# robotario-2.net
KiCad netlist of a schematic drawn in EAGLE
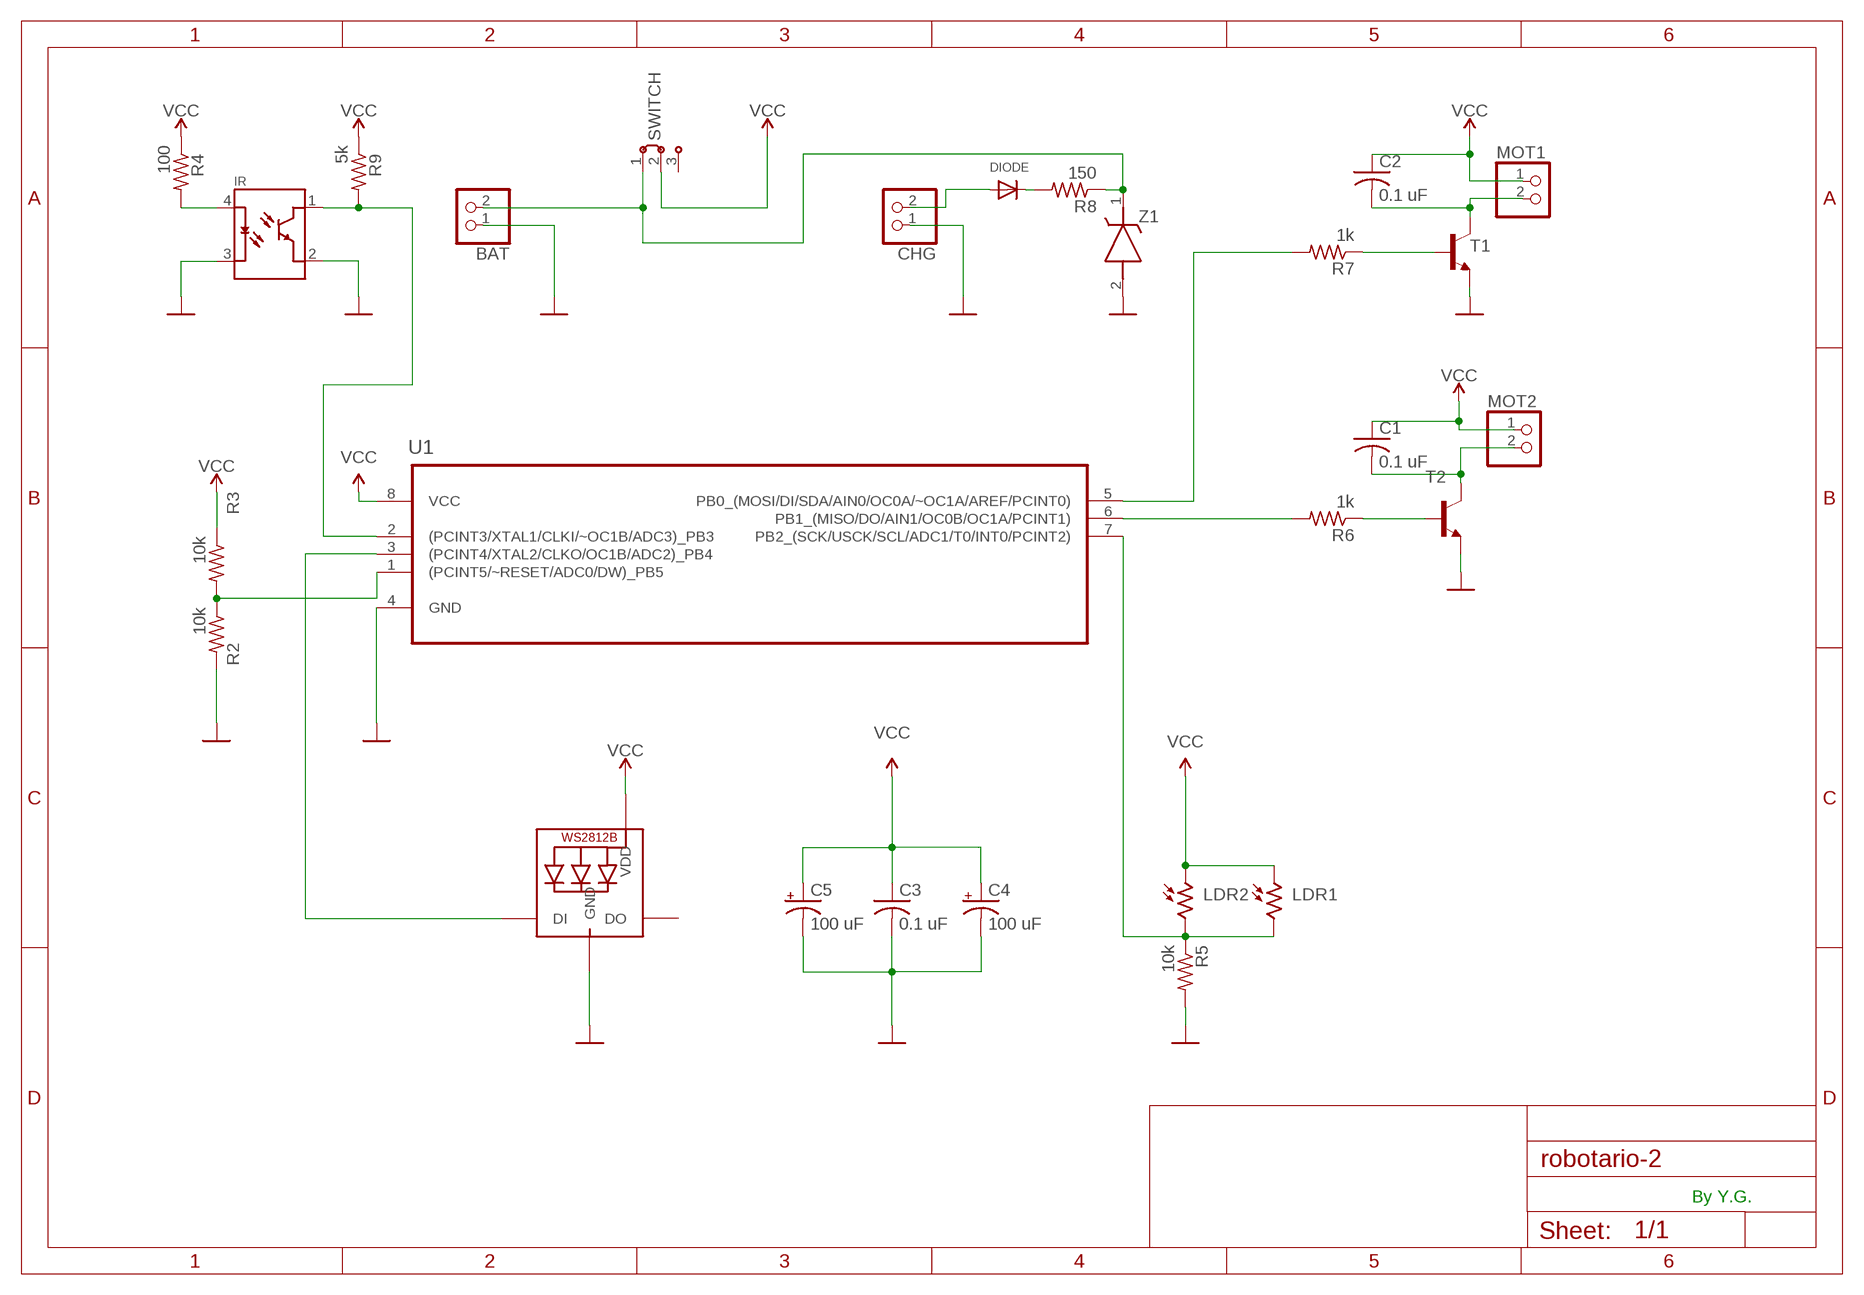
[diagram p0: schematic, sheet 1]

(export (version "E")
  (design (tool "Eeschema 10.0.6"))
  (components
    (comp (ref "BAT")
      (value "PINHD-1X2")
      (footprint "eagle-import:1X02")
      (libsource (lib "eagle-import") (part "PINHD-1X2"))
    )
    (comp (ref "C1")
      (value "0.1 uF")
      (footprint "eagle-import:C050-024X044")
      (libsource (lib "eagle-import") (part "C-US050-024X044"))
    )
    (comp (ref "C2")
      (value "0.1 uF")
      (footprint "eagle-import:C050-024X044")
      (libsource (lib "eagle-import") (part "C-US050-024X044"))
    )
    (comp (ref "C3")
      (value "0.1 uF")
      (footprint "eagle-import:C050-024X044")
      (libsource (lib "eagle-import") (part "C-US050-024X044"))
    )
    (comp (ref "C4")
      (value "100 uF")
      (footprint "eagle-import:E5-5")
      (libsource (lib "eagle-import") (part "CPOL-USE5-5"))
    )
    (comp (ref "C5")
      (value "100 uF")
      (footprint "eagle-import:E5-5")
      (libsource (lib "eagle-import") (part "CPOL-USE5-5"))
    )
    (comp (ref "CHG")
      (value "PINHD-1X2")
      (footprint "eagle-import:1X02")
      (libsource (lib "eagle-import") (part "PINHD-1X2"))
    )
    (comp (ref "DIODE")
      (value "DIODEDO-1N4148")
      (footprint "eagle-import:DO-1N4148")
      (libsource (lib "eagle-import") (part "DIODEDO-1N4148"))
    )
    (comp (ref "IR")
      (value "TCRT5000L")
      (footprint "eagle-import:XDCR_TCRT5000L")
      (fields (field (name "MF") "Vishay"))
      (libsource (lib "eagle-import") (part "TCRT5000L"))
    )
    (comp (ref "LDR1")
      (value "A1050_14")
      (footprint "eagle-import:T0-46-A10XX")
      (libsource (lib "eagle-import") (part "A1050_14"))
    )
    (comp (ref "LDR2")
      (value "A1050_14")
      (footprint "eagle-import:T0-46-A10XX")
      (libsource (lib "eagle-import") (part "A1050_14"))
    )
    (comp (ref "LED2")
      (value "WS2812B5050")
      (footprint "eagle-import:WS2812B")
      (fields (field (name "MF") "SparkFun Electronics") (field (name "MP") "WS2812B"))
      (libsource (lib "eagle-import") (part "WS2812B5050"))
    )
    (comp (ref "MOT1")
      (value "PINHD-1X2")
      (footprint "eagle-import:1X02")
      (libsource (lib "eagle-import") (part "PINHD-1X2"))
    )
    (comp (ref "MOT2")
      (value "PINHD-1X2")
      (footprint "eagle-import:1X02")
      (libsource (lib "eagle-import") (part "PINHD-1X2"))
    )
    (comp (ref "R2")
      (value "10k")
      (footprint "eagle-import:0207_10")
      (libsource (lib "eagle-import") (part "R-US_0207/10"))
    )
    (comp (ref "R3")
      (value "10k")
      (footprint "eagle-import:0207_10")
      (libsource (lib "eagle-import") (part "R-US_0207/10"))
    )
    (comp (ref "R4")
      (value "100")
      (footprint "eagle-import:0207_10")
      (libsource (lib "eagle-import") (part "R-US_0207/10"))
    )
    (comp (ref "R5")
      (value "10k")
      (footprint "eagle-import:0207_10")
      (libsource (lib "eagle-import") (part "R-US_0207/10"))
    )
    (comp (ref "R6")
      (value "1k")
      (footprint "eagle-import:0207_10")
      (libsource (lib "eagle-import") (part "R-US_0207/10"))
    )
    (comp (ref "R7")
      (value "1k")
      (footprint "eagle-import:0207_10")
      (libsource (lib "eagle-import") (part "R-US_0207/10"))
    )
    (comp (ref "R8")
      (value "150")
      (footprint "eagle-import:0207_10")
      (libsource (lib "eagle-import") (part "R-US_0207/10"))
    )
    (comp (ref "R9")
      (value "5k")
      (footprint "eagle-import:0207_10")
      (libsource (lib "eagle-import") (part "R-US_0207/10"))
    )
    (comp (ref "SWITCH")
      (value "J2X2MM")
      (footprint "eagle-import:04C")
      (libsource (lib "eagle-import") (part "J2X2MM"))
    )
    (comp (ref "T1")
      (value "2N3904")
      (footprint "eagle-import:TO92")
      (libsource (lib "eagle-import") (part "2N3904"))
    )
    (comp (ref "T2")
      (value "2N3904")
      (footprint "eagle-import:TO92")
      (libsource (lib "eagle-import") (part "2N3904"))
    )
    (comp (ref "U1")
      (value "ATTINY85-20PU")
      (footprint "eagle-import:DIP254P762X533-8")
      (fields (field (name "MF") "Microchip"))
      (libsource (lib "eagle-import") (part "ATTINY85-20PU"))
    )
    (comp (ref "Z1")
      (value "NZX4V3C")
      (footprint "eagle-import:DIOAD950W60L350D150")
      (fields
        (field (name "DIGI-KEY_PART_NUMBER") "BZX55C10-GICT-ND")
        (field (name "MF") "Vishay Semiconductor")
        (field (name "MP") "BZX55C10-TR")
      )
      (libsource (lib "eagle-import") (part "BZX55C10"))
    )
  )
  (nets
    (net (code "1") (name "GND") (class "Default")
      (node (ref "BAT") (pin "1") (pinfunction "1_1") (pintype "passive"))
      (node (ref "C3") (pin "2") (pinfunction "2_2") (pintype "passive"))
      (node (ref "C4") (pin "-") (pinfunction "-_-") (pintype "passive"))
      (node (ref "C5") (pin "-") (pinfunction "-_-") (pintype "passive"))
      (node (ref "CHG") (pin "1") (pinfunction "1_1") (pintype "passive"))
      (node (ref "IR") (pin "2") (pinfunction "E_2") (pintype "passive"))
      (node (ref "IR") (pin "3") (pinfunction "C_3") (pintype "passive"))
      (node (ref "LED2") (pin "3-GND") (pinfunction "GND_3-GND") (pintype "power_in"))
      (node (ref "R2") (pin "2") (pinfunction "2_2") (pintype "passive"))
      (node (ref "R5") (pin "2") (pinfunction "2_2") (pintype "passive"))
      (node (ref "T1") (pin "3") (pinfunction "E_3") (pintype "passive"))
      (node (ref "T2") (pin "3") (pinfunction "E_3") (pintype "passive"))
      (node (ref "U1") (pin "4") (pinfunction "GND_4") (pintype "passive"))
      (node (ref "Z1") (pin "2") (pinfunction "A_2") (pintype "bidirectional"))
    )
    (net (code "2") (name "Net-(CHG-Pad2)") (class "Default")
      (node (ref "CHG") (pin "2") (pinfunction "2_2") (pintype "passive"))
      (node (ref "DIODE") (pin "A") (pinfunction "A_A") (pintype "passive"))
    )
    (net (code "3") (name "Net-(DIODE-PadC)") (class "Default")
      (node (ref "DIODE") (pin "C") (pinfunction "C_C") (pintype "passive"))
      (node (ref "R8") (pin "2") (pinfunction "2_2") (pintype "passive"))
    )
    (net (code "4") (name "Net-(IR-A)") (class "Default")
      (node (ref "IR") (pin "4") (pinfunction "A_4") (pintype "passive"))
      (node (ref "R4") (pin "2") (pinfunction "2_2") (pintype "passive"))
    )
    (net (code "5") (name "Net-(IR-CO)") (class "Default")
      (node (ref "IR") (pin "1") (pinfunction "CO_1") (pintype "passive"))
      (node (ref "R9") (pin "2") (pinfunction "2_2") (pintype "passive"))
      (node (ref "U1") (pin "2") (pinfunction "(PCINT3/XTAL1/CLKI/~{OC1B/ADC3})_PB3_2") (pintype "bidirectional"))
    )
    (net (code "6") (name "Net-(LED2-DI)") (class "Default")
      (node (ref "LED2") (pin "4-DIN") (pinfunction "DI_4-DIN") (pintype "input"))
      (node (ref "U1") (pin "3") (pinfunction "(PCINT4/XTAL2/CLKO/OC1B/ADC2)_PB4_3") (pintype "bidirectional"))
    )
    (net (code "7") (name "Net-(T1-B)") (class "Default")
      (node (ref "R7") (pin "1") (pinfunction "1_1") (pintype "passive"))
      (node (ref "T1") (pin "2") (pinfunction "B_2") (pintype "passive"))
    )
    (net (code "8") (name "Net-(T1-C)") (class "Default")
      (node (ref "C2") (pin "2") (pinfunction "2_2") (pintype "passive"))
      (node (ref "MOT1") (pin "2") (pinfunction "2_2") (pintype "passive"))
      (node (ref "T1") (pin "1") (pinfunction "C_1") (pintype "passive"))
    )
    (net (code "9") (name "Net-(T2-B)") (class "Default")
      (node (ref "R6") (pin "1") (pinfunction "1_1") (pintype "passive"))
      (node (ref "T2") (pin "2") (pinfunction "B_2") (pintype "passive"))
    )
    (net (code "10") (name "Net-(T2-C)") (class "Default")
      (node (ref "C1") (pin "2") (pinfunction "2_2") (pintype "passive"))
      (node (ref "MOT2") (pin "2") (pinfunction "2_2") (pintype "passive"))
      (node (ref "T2") (pin "1") (pinfunction "C_1") (pintype "passive"))
    )
    (net (code "11") (name "Net-(U1-(PCINT5{slash}~{RESET{slash}ADC0{slash}DW})_PB5)") (class "Default")
      (node (ref "R2") (pin "1") (pinfunction "1_1") (pintype "passive"))
      (node (ref "R3") (pin "2") (pinfunction "2_2") (pintype "passive"))
      (node (ref "U1") (pin "1") (pinfunction "(PCINT5/~{RESET/ADC0/DW})_PB5_1") (pintype "bidirectional"))
    )
    (net (code "12") (name "Net-(U1-PB0_(MOSI{slash}DI{slash}SDA{slash}AIN0{slash}OC0A{slash}~{OC1A{slash}AREF{slash}PCINT0}))") (class "Default")
      (node (ref "R7") (pin "2") (pinfunction "2_2") (pintype "passive"))
      (node (ref "U1") (pin "5") (pinfunction "PB0_(MOSI/DI/SDA/AIN0/OC0A/~{OC1A/AREF/PCINT0})_5") (pintype "bidirectional"))
    )
    (net (code "13") (name "Net-(U1-PB1_(MISO{slash}DO{slash}AIN1{slash}OC0B{slash}OC1A{slash}PCINT1))") (class "Default")
      (node (ref "R6") (pin "2") (pinfunction "2_2") (pintype "passive"))
      (node (ref "U1") (pin "6") (pinfunction "PB1_(MISO/DO/AIN1/OC0B/OC1A/PCINT1)_6") (pintype "bidirectional"))
    )
    (net (code "14") (name "Net-(U1-PB2_(SCK{slash}USCK{slash}SCL{slash}ADC1{slash}T0{slash}INT0{slash}PCINT2))") (class "Default")
      (node (ref "LDR1") (pin "2") (pinfunction "2_2") (pintype "passive"))
      (node (ref "LDR2") (pin "2") (pinfunction "2_2") (pintype "passive"))
      (node (ref "R5") (pin "1") (pinfunction "1_1") (pintype "passive"))
      (node (ref "U1") (pin "7") (pinfunction "PB2_(SCK/USCK/SCL/ADC1/T0/INT0/PCINT2)_7") (pintype "bidirectional"))
    )
    (net (code "15") (name "Net-(Z1-K)") (class "Default")
      (node (ref "BAT") (pin "2") (pinfunction "2_2") (pintype "passive"))
      (node (ref "R8") (pin "1") (pinfunction "1_1") (pintype "passive"))
      (node (ref "SWITCH") (pin "1") (pinfunction "1_1") (pintype "passive"))
      (node (ref "Z1") (pin "1") (pinfunction "K_1") (pintype "bidirectional"))
    )
    (net (code "16") (name "VCC") (class "Default")
      (node (ref "C1") (pin "1") (pinfunction "1_1") (pintype "passive"))
      (node (ref "C2") (pin "1") (pinfunction "1_1") (pintype "passive"))
      (node (ref "C3") (pin "1") (pinfunction "1_1") (pintype "passive"))
      (node (ref "C4") (pin "+") (pinfunction "+_+") (pintype "passive"))
      (node (ref "C5") (pin "+") (pinfunction "+_+") (pintype "passive"))
      (node (ref "LDR1") (pin "1") (pinfunction "1_1") (pintype "passive"))
      (node (ref "LDR2") (pin "1") (pinfunction "1_1") (pintype "passive"))
      (node (ref "LED2") (pin "1-VDD") (pinfunction "VDD_1-VDD") (pintype "power_in"))
      (node (ref "MOT1") (pin "1") (pinfunction "1_1") (pintype "passive"))
      (node (ref "MOT2") (pin "1") (pinfunction "1_1") (pintype "passive"))
      (node (ref "R3") (pin "1") (pinfunction "1_1") (pintype "passive"))
      (node (ref "R4") (pin "1") (pinfunction "1_1") (pintype "passive"))
      (node (ref "R9") (pin "1") (pinfunction "1_1") (pintype "passive"))
      (node (ref "SWITCH") (pin "2") (pinfunction "2_2") (pintype "passive"))
      (node (ref "U1") (pin "8") (pinfunction "VCC_8") (pintype "power_in"))
    )
    (net (code "17") (name "unconnected-(LED2-DO-Pad2-DOUT)") (class "Default")
      (node (ref "LED2") (pin "2-DOUT") (pinfunction "DO_2-DOUT") (pintype "output"))
    )
    (net (code "18") (name "unconnected-(SWITCH-Pad3)") (class "Default")
      (node (ref "SWITCH") (pin "3") (pinfunction "3_3") (pintype "passive"))
    )
  )
)
